# ProPrj.net
KiCad netlist of a schematic drawn in EasyEDA Pro
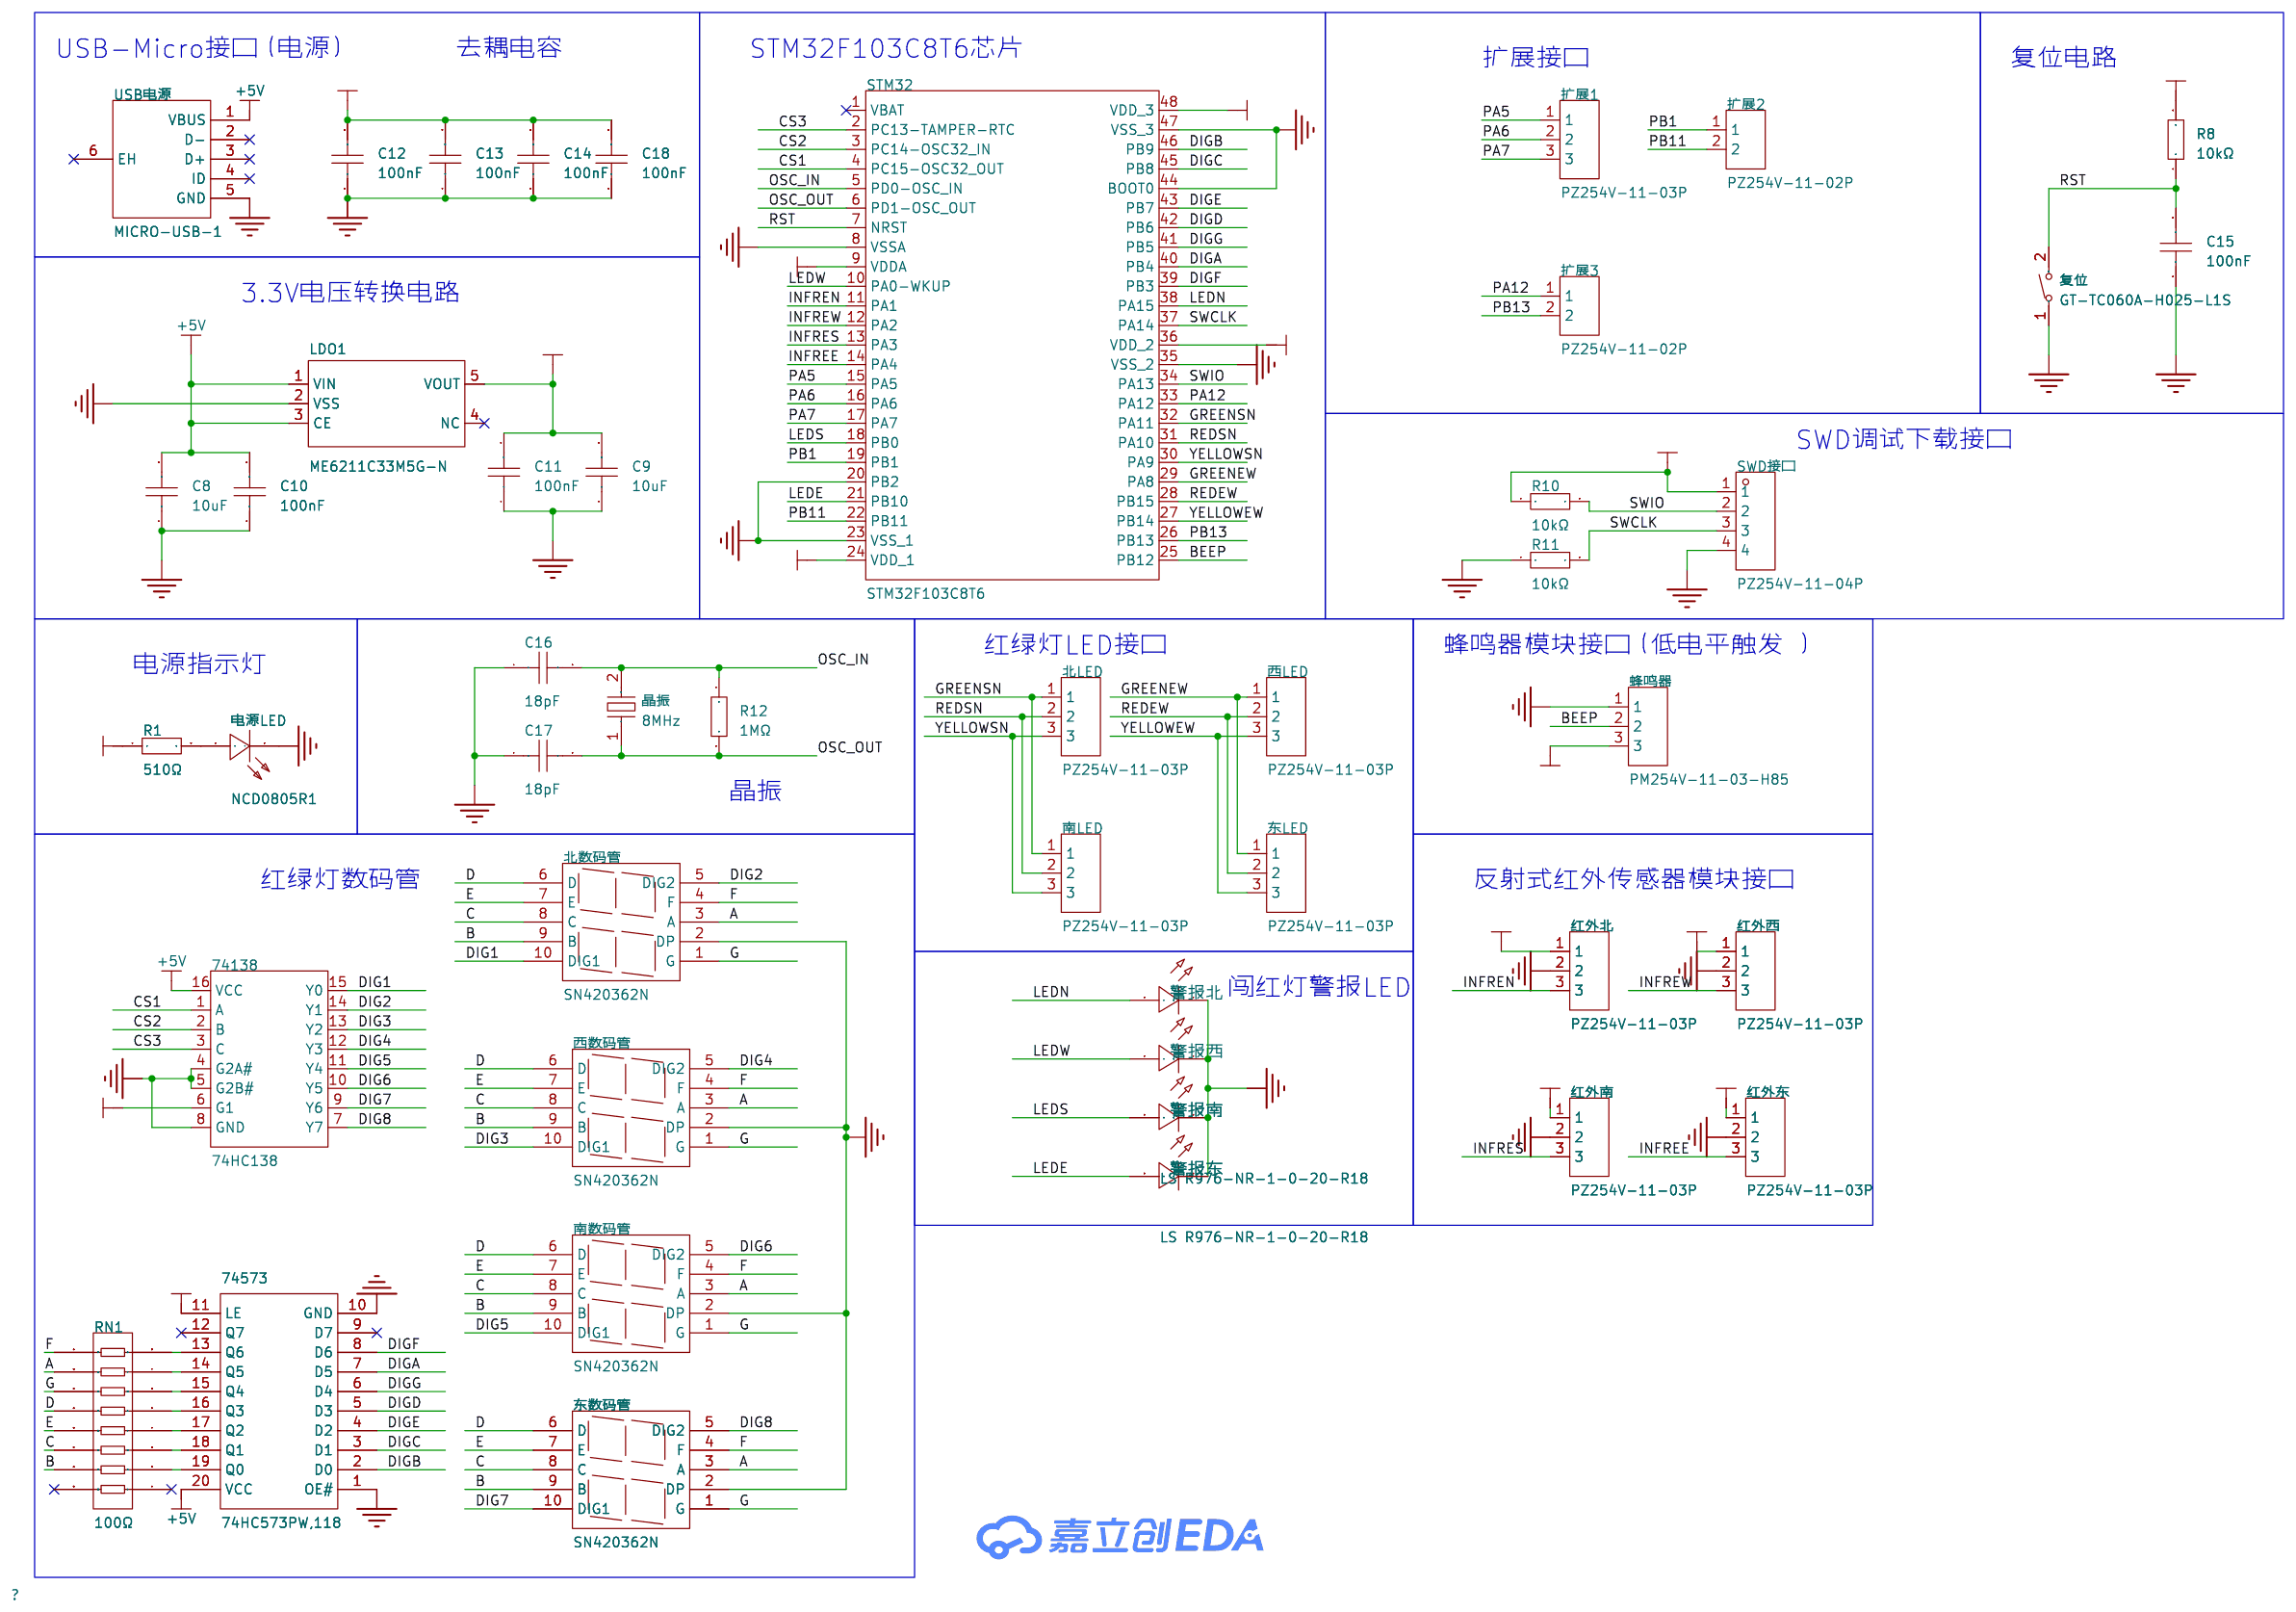
[diagram p0: schematic sheet]

(export (version "E")
  (design (tool "Eeschema 10.0.6"))
  (components
    (comp (ref "74138")
      (value "74HC138")
      (footprint "easyedapro:SOP-16_L10.0-W3.9-P1.27-LS6.0-BL")
      (description "供电电压:2V~6V;线路数:3~8;灌电流(IOL):5.2mA;拉电流(IOH):5.2mA;")
      (fields (field (name "Manufacturer") "GR(国睿)"))
      (libsource (lib "easyedapro") (part "74HC138_C18164491"))
    )
    (comp (ref "74573")
      (value "74HC573PW,118")
      (footprint "easyedapro:TSSOP-20_L6.5-W4.4-P0.65-LS6.4-BL")
      (description "逻辑类型:D型锁存器;电源电压:2V~6V;通道数:8;传播延迟:14ns;")
      (fields (field (name "Manufacturer") "Nexperia(安世)"))
      (libsource (lib "easyedapro") (part "74HC573PW,118"))
    )
    (comp (ref "C8")
      (value "10uF")
      (footprint "easyedapro:C0805")
      (description "容值:10uF;精度:±10%;额定电压:25V;温度系数:X5R;")
      (fields
        (field (name "Manufacturer Part") "CGA0805X5R106K250MT")
        (field (name "Manufacturer") "HRE(芯声)")
      )
      (libsource (lib "easyedapro") (part "CGA0805X5R106K250MT"))
    )
    (comp (ref "C9")
      (value "10uF")
      (footprint "easyedapro:C0805")
      (description "容值:10uF;精度:±10%;额定电压:25V;温度系数:X5R;")
      (fields
        (field (name "Manufacturer Part") "CGA0805X5R106K250MT")
        (field (name "Manufacturer") "HRE(芯声)")
      )
      (libsource (lib "easyedapro") (part "CGA0805X5R106K250MT"))
    )
    (comp (ref "C10")
      (value "100nF")
      (footprint "easyedapro:C0805")
      (description "容值:100nF;精度:±10%;额定电压:50V;材质(温度系数):X7R;")
      (fields
        (field (name "Manufacturer Part") "CC0805KRX7R9BB104")
        (field (name "Manufacturer") "YAGEO(国巨)")
      )
      (libsource (lib "easyedapro") (part "CC0805KRX7R9BB104"))
    )
    (comp (ref "C11")
      (value "100nF")
      (footprint "easyedapro:C0805")
      (description "容值:100nF;精度:±10%;额定电压:50V;材质(温度系数):X7R;")
      (fields
        (field (name "Manufacturer Part") "CC0805KRX7R9BB104")
        (field (name "Manufacturer") "YAGEO(国巨)")
      )
      (libsource (lib "easyedapro") (part "CC0805KRX7R9BB104"))
    )
    (comp (ref "C12")
      (value "100nF")
      (footprint "easyedapro:C0805")
      (description "容值:100nF;精度:±10%;额定电压:50V;材质(温度系数):X7R;")
      (fields
        (field (name "Manufacturer Part") "CC0805KRX7R9BB104")
        (field (name "Manufacturer") "YAGEO(国巨)")
      )
      (libsource (lib "easyedapro") (part "CC0805KRX7R9BB104"))
    )
    (comp (ref "C13")
      (value "100nF")
      (footprint "easyedapro:C0805")
      (description "容值:100nF;精度:±10%;额定电压:50V;材质(温度系数):X7R;")
      (fields
        (field (name "Manufacturer Part") "CC0805KRX7R9BB104")
        (field (name "Manufacturer") "YAGEO(国巨)")
      )
      (libsource (lib "easyedapro") (part "CC0805KRX7R9BB104"))
    )
    (comp (ref "C14")
      (value "100nF")
      (footprint "easyedapro:C0805")
      (description "容值:100nF;精度:±10%;额定电压:50V;材质(温度系数):X7R;")
      (fields
        (field (name "Manufacturer Part") "CC0805KRX7R9BB104")
        (field (name "Manufacturer") "YAGEO(国巨)")
      )
      (libsource (lib "easyedapro") (part "CC0805KRX7R9BB104"))
    )
    (comp (ref "C15")
      (value "100nF")
      (footprint "easyedapro:C0805")
      (description "容值:100nF;精度:±10%;额定电压:50V;材质(温度系数):X7R;")
      (fields
        (field (name "Manufacturer Part") "CC0805KRX7R9BB104")
        (field (name "Manufacturer") "YAGEO(国巨)")
      )
      (libsource (lib "easyedapro") (part "CC0805KRX7R9BB104"))
    )
    (comp (ref "C16")
      (value "18pF")
      (footprint "easyedapro:C0805")
      (description "容值:18pF;精度:±5%;额定电压:50V;温度系数:C0G;")
      (fields
        (field (name "Manufacturer Part") "CGA0805C0G180J500HT")
        (field (name "Manufacturer") "HRE(芯声)")
      )
      (libsource (lib "easyedapro") (part "CGA0805C0G180J500HT"))
    )
    (comp (ref "C17")
      (value "18pF")
      (footprint "easyedapro:C0805")
      (description "容值:18pF;精度:±5%;额定电压:50V;温度系数:C0G;")
      (fields
        (field (name "Manufacturer Part") "CGA0805C0G180J500HT")
        (field (name "Manufacturer") "HRE(芯声)")
      )
      (libsource (lib "easyedapro") (part "CGA0805C0G180J500HT"))
    )
    (comp (ref "C18")
      (value "100nF")
      (footprint "easyedapro:C0805")
      (description "容值:100nF;精度:±10%;额定电压:50V;材质(温度系数):X7R;")
      (fields
        (field (name "Manufacturer Part") "CC0805KRX7R9BB104")
        (field (name "Manufacturer") "YAGEO(国巨)")
      )
      (libsource (lib "easyedapro") (part "CC0805KRX7R9BB104"))
    )
    (comp (ref "LDO1")
      (value "ME6211C33M5G-N")
      (footprint "easyedapro:SOT-23-5_L3.0-W1.7-P0.95-LS2.8-BL")
      (description "输出类型:固定;工作电压:6V;输出电压:3.3V;输出电流:500mA;电源纹波抑制比(PSRR):70dB@(1kHz)；62dB@(10kHz);输出极性:正极;")
      (fields (field (name "Manufacturer") "MICRONE(南京微盟)"))
      (libsource (lib "easyedapro") (part "ME6211C33M5G-N"))
    )
    (comp (ref "R1")
      (value "510Ω")
      (footprint "easyedapro:R0805")
      (description "电阻类型:厚膜电阻;阻值:510Ω;精度:±1%;功率:125mW;最大工作电压:150V;温度系数:±100ppm/°C;")
      (fields
        (field (name "Manufacturer Part") "0805W8F5100T5E")
        (field (name "Manufacturer") "UNI-ROYAL(厚声)")
      )
      (libsource (lib "easyedapro") (part "0805W8F5100T5E"))
    )
    (comp (ref "R8")
      (value "10kΩ")
      (footprint "easyedapro:R0805")
      (description "电阻类型:厚膜电阻;阻值:10kΩ;精度:±1%;功率:125mW;最大工作电压:150V;温度系数:±100ppm/°C;")
      (fields
        (field (name "Manufacturer Part") "0805W8F1002T5E")
        (field (name "Manufacturer") "UNI-ROYAL(厚声)")
      )
      (libsource (lib "easyedapro") (part "0805W8F1002T5E"))
    )
    (comp (ref "R10")
      (value "10kΩ")
      (footprint "easyedapro:R0805")
      (description "电阻类型:厚膜电阻;阻值:10kΩ;精度:±1%;功率:125mW;最大工作电压:150V;温度系数:±100ppm/°C;")
      (fields
        (field (name "Manufacturer Part") "0805W8F1002T5E")
        (field (name "Manufacturer") "UNI-ROYAL(厚声)")
      )
      (libsource (lib "easyedapro") (part "0805W8F1002T5E"))
    )
    (comp (ref "R11")
      (value "10kΩ")
      (footprint "easyedapro:R0805")
      (description "电阻类型:厚膜电阻;阻值:10kΩ;精度:±1%;功率:125mW;最大工作电压:150V;温度系数:±100ppm/°C;")
      (fields
        (field (name "Manufacturer Part") "0805W8F1002T5E")
        (field (name "Manufacturer") "UNI-ROYAL(厚声)")
      )
      (libsource (lib "easyedapro") (part "0805W8F1002T5E"))
    )
    (comp (ref "R12")
      (value "1MΩ")
      (footprint "easyedapro:R0805")
      (description "电阻类型:厚膜电阻;阻值:1MΩ;精度:±1%;功率:125mW;最大工作电压:150V;温度系数:±100ppm/°C;")
      (fields
        (field (name "Manufacturer Part") "0805W8F1004T5E")
        (field (name "Manufacturer") "UNI-ROYAL(厚声)")
      )
      (libsource (lib "easyedapro") (part "0805W8F1004T5E"))
    )
    (comp (ref "RN1")
      (value "100Ω")
      (footprint "easyedapro:RES-ARRAY-SMD_16P-L3.8-W1.6-P0.50-BL")
      (description "电阻器数:8;阻值:100Ω;精度:±5%;单个元件功率:63mW;温度系数:±100ppm/°C;")
      (fields (field (name "Manufacturer Part") "EXB2HV101JV") (field (name "Manufacturer") "PANASONIC(松下)"))
      (libsource (lib "easyedapro") (part "EXB2HV101JV"))
    )
    (comp (ref "STM32")
      (value "STM32F103C8T6")
      (footprint "easyedapro:LQFP-48_L7.0-W7.0-P0.50-LS9.0-BL")
      (description "CPU内核:ARM-M3;CPU最大主频:72MHz;应用领域:-;")
      (fields (field (name "Manufacturer") "ST(意法半导体)"))
      (libsource (lib "easyedapro") (part "STM32F103C8T6"))
    )
    (comp (ref "SWD接口")
      (value "PZ254V-11-04P")
      (footprint "easyedapro:HDR-TH_4P-P2.54-V-M")
      (fields (field (name "Manufacturer") "XFCN(兴飞)"))
      (libsource (lib "easyedapro") (part "PZ254V-11-04P_C2691448"))
    )
    (comp (ref "USB电源")
      (value "MICRO-USB-1")
      (footprint "easyedapro:MICRO-USB-SMD_C9900008946")
      (libsource (lib "easyedapro") (part "MICRO-USB-1"))
    )
    (comp (ref "东LED")
      (value "PZ254V-11-03P")
      (footprint "easyedapro:HDR-TH_3P-P2.54-V-M")
      (fields (field (name "Manufacturer") "XFCN(兴飞)"))
      (libsource (lib "easyedapro") (part "PZ254V-11-03P_C2937625"))
    )
    (comp (ref "东数码管")
      (value "SN420362N")
      (footprint "easyedapro:LED-SEG-TH_10P-L15.0-W14.0-P2.54-S10.16-BL")
      (description "数码管位数:2位;耗散功率(Pd):50mW;发光颜色:红色;LED极性:共阴极;数字/字母大小(英寸):0.36;")
      (fields (field (name "Manufacturer") "ARKLED(方舟)"))
      (libsource (lib "easyedapro") (part "SN420362N"))
    )
    (comp (ref "北LED")
      (value "PZ254V-11-03P")
      (footprint "easyedapro:HDR-TH_3P-P2.54-V-M")
      (fields (field (name "Manufacturer") "XFCN(兴飞)"))
      (libsource (lib "easyedapro") (part "PZ254V-11-03P_C2937625"))
    )
    (comp (ref "北数码管")
      (value "SN420362N")
      (footprint "easyedapro:LED-SEG-TH_10P-L15.0-W14.0-P2.54-S10.16-BL")
      (description "数码管位数:2位;耗散功率(Pd):50mW;发光颜色:红色;LED极性:共阴极;数字/字母大小(英寸):0.36;")
      (fields (field (name "Manufacturer") "ARKLED(方舟)"))
      (libsource (lib "easyedapro") (part "SN420362N"))
    )
    (comp (ref "南LED")
      (value "PZ254V-11-03P")
      (footprint "easyedapro:HDR-TH_3P-P2.54-V-M")
      (fields (field (name "Manufacturer") "XFCN(兴飞)"))
      (libsource (lib "easyedapro") (part "PZ254V-11-03P_C2937625"))
    )
    (comp (ref "南数码管")
      (value "SN420362N")
      (footprint "easyedapro:LED-SEG-TH_10P-L15.0-W14.0-P2.54-S10.16-BL")
      (description "数码管位数:2位;耗散功率(Pd):50mW;发光颜色:红色;LED极性:共阴极;数字/字母大小(英寸):0.36;")
      (fields (field (name "Manufacturer") "ARKLED(方舟)"))
      (libsource (lib "easyedapro") (part "SN420362N"))
    )
    (comp (ref "复位")
      (value "GT-TC060A-H025-L1S")
      (footprint "easyedapro:SW-SMD_L6.1-W3.5-LS8.0")
      (description "电路结构:单刀单掷;作用力:1.6N;安装方式:立贴;带支架:不带;触点电流:50mA;额定电压(AC):12V;额定电压(DC):12V;绝缘电阻:100MΩ;带灯:无;机械寿命:10万次;")
      (fields (field (name "Manufacturer") "G-Switch(品赞)"))
      (libsource (lib "easyedapro") (part "GT-TC060A-H025-L1S"))
    )
    (comp (ref "扩展1")
      (value "PZ254V-11-03P")
      (footprint "easyedapro:HDR-TH_3P-P2.54-V-M")
      (fields (field (name "Manufacturer") "XFCN(兴飞)"))
      (libsource (lib "easyedapro") (part "PZ254V-11-03P_C2937625"))
    )
    (comp (ref "扩展2")
      (value "PZ254V-11-02P")
      (footprint "easyedapro:HDR-TH_2P-P2.54-V-M")
      (fields (field (name "Manufacturer") "XFCN(兴飞)"))
      (libsource (lib "easyedapro") (part "PZ254V-11-02P"))
    )
    (comp (ref "扩展3")
      (value "PZ254V-11-02P")
      (footprint "easyedapro:HDR-TH_2P-P2.54-V-M")
      (fields (field (name "Manufacturer") "XFCN(兴飞)"))
      (libsource (lib "easyedapro") (part "PZ254V-11-02P"))
    )
    (comp (ref "晶振")
      (value "8MHz")
      (footprint "easyedapro:HC-49US_L11.5-W4.5-P4.88")
      (description "频率:8MHz;常温频差:±20ppm;负载电容:18pF;频率稳定度(全温):±50ppm;")
      (fields (field (name "Manufacturer Part") "ABL-8.000MHZ-B2-T") (field (name "Manufacturer") "ABRACON"))
      (libsource (lib "easyedapro") (part "ABL-8.000MHZ-B2-T"))
    )
    (comp (ref "电源LED")
      (value "NCD0805R1")
      (footprint "easyedapro:LED0805-R-RD")
      (fields (field (name "Manufacturer") "国星光电"))
      (libsource (lib "easyedapro") (part "FC-2012HRK-620D"))
    )
    (comp (ref "红外东")
      (value "PZ254V-11-03P")
      (footprint "easyedapro:HDR-TH_3P-P2.54-V-M")
      (fields (field (name "Manufacturer") "XFCN(兴飞)"))
      (libsource (lib "easyedapro") (part "PZ254V-11-03P_C2937625"))
    )
    (comp (ref "红外北")
      (value "PZ254V-11-03P")
      (footprint "easyedapro:HDR-TH_3P-P2.54-V-M")
      (fields (field (name "Manufacturer") "XFCN(兴飞)"))
      (libsource (lib "easyedapro") (part "PZ254V-11-03P_C2937625"))
    )
    (comp (ref "红外南")
      (value "PZ254V-11-03P")
      (footprint "easyedapro:HDR-TH_3P-P2.54-V-M")
      (fields (field (name "Manufacturer") "XFCN(兴飞)"))
      (libsource (lib "easyedapro") (part "PZ254V-11-03P_C2937625"))
    )
    (comp (ref "红外西")
      (value "PZ254V-11-03P")
      (footprint "easyedapro:HDR-TH_3P-P2.54-V-M")
      (fields (field (name "Manufacturer") "XFCN(兴飞)"))
      (libsource (lib "easyedapro") (part "PZ254V-11-03P_C2937625"))
    )
    (comp (ref "蜂鸣器")
      (value "PM254V-11-03-H85")
      (footprint "easyedapro:HDR-TH_3P-P2.54-V-F")
      (description "插孔结构:1x3P;间距:2.54mm;行距:-;安装类型:直插;排数:单排;总孔位数:3P;塑高:-;触头材质:黄铜;触头镀层:-;")
      (fields (field (name "Manufacturer") "XFCN(兴飞)"))
      (libsource (lib "easyedapro") (part "PM254V-11-03-H85"))
    )
    (comp (ref "西LED")
      (value "PZ254V-11-03P")
      (footprint "easyedapro:HDR-TH_3P-P2.54-V-M")
      (fields (field (name "Manufacturer") "XFCN(兴飞)"))
      (libsource (lib "easyedapro") (part "PZ254V-11-03P_C2937625"))
    )
    (comp (ref "西数码管")
      (value "SN420362N")
      (footprint "easyedapro:LED-SEG-TH_10P-L15.0-W14.0-P2.54-S10.16-BL")
      (description "数码管位数:2位;耗散功率(Pd):50mW;发光颜色:红色;LED极性:共阴极;数字/字母大小(英寸):0.36;")
      (fields (field (name "Manufacturer") "ARKLED(方舟)"))
      (libsource (lib "easyedapro") (part "SN420362N"))
    )
    (comp (ref "警报东")
      (value "LS R976-NR-1-0-20-R18")
      (footprint "easyedapro:LED_0805")
      (fields (field (name "Manufacturer") "OSRAM(欧司朗)"))
      (libsource (lib "easyedapro") (part "LED_R"))
    )
    (comp (ref "警报北")
      (value "北")
      (footprint "easyedapro:LED_0805")
      (libsource (lib "easyedapro") (part "LED_R"))
    )
    (comp (ref "警报南")
      (value "LS R976-NR-1-0-20-R18")
      (footprint "easyedapro:LED_0805")
      (fields (field (name "Manufacturer") "OSRAM(欧司朗)"))
      (libsource (lib "easyedapro") (part "LED_R"))
    )
    (comp (ref "警报西")
      (value "西")
      (footprint "easyedapro:LED_0805")
      (libsource (lib "easyedapro") (part "LED_R"))
    )
  )
  (nets
    (net (code "1") (name "+5V") (class "Default")
      (node (ref "74138") (pin "16") (pinfunction "VCC_16") (pintype "unspecified"))
      (node (ref "74573") (pin "20") (pinfunction "VCC_20") (pintype "unspecified"))
      (node (ref "C10") (pin "2") (pinfunction "2_2") (pintype "unspecified"))
      (node (ref "C8") (pin "2") (pinfunction "2_2") (pintype "unspecified"))
      (node (ref "LDO1") (pin "1") (pinfunction "VIN_1") (pintype "unspecified"))
      (node (ref "LDO1") (pin "3") (pinfunction "CE_3") (pintype "unspecified"))
      (node (ref "USB电源") (pin "1") (pinfunction "VBUS_1") (pintype "input"))
    )
    (net (code "2") (name "/A") (class "Default")
      (node (ref "RN1") (pin "10") (pinfunction "10_10") (pintype "unspecified"))
      (node (ref "东数码管") (pin "3") (pinfunction "A_3") (pintype "unspecified"))
      (node (ref "北数码管") (pin "3") (pinfunction "A_3") (pintype "unspecified"))
      (node (ref "南数码管") (pin "3") (pinfunction "A_3") (pintype "unspecified"))
      (node (ref "西数码管") (pin "3") (pinfunction "A_3") (pintype "unspecified"))
    )
    (net (code "3") (name "/B") (class "Default")
      (node (ref "RN1") (pin "15") (pinfunction "15_15") (pintype "unspecified"))
      (node (ref "东数码管") (pin "9") (pinfunction "B_9") (pintype "unspecified"))
      (node (ref "北数码管") (pin "9") (pinfunction "B_9") (pintype "unspecified"))
      (node (ref "南数码管") (pin "9") (pinfunction "B_9") (pintype "unspecified"))
      (node (ref "西数码管") (pin "9") (pinfunction "B_9") (pintype "unspecified"))
    )
    (net (code "4") (name "/BEEP") (class "Default")
      (node (ref "STM32") (pin "25") (pinfunction "PB12_25") (pintype "unspecified"))
      (node (ref "蜂鸣器") (pin "2") (pinfunction "2_2") (pintype "unspecified"))
    )
    (net (code "5") (name "/C") (class "Default")
      (node (ref "RN1") (pin "14") (pinfunction "14_14") (pintype "unspecified"))
      (node (ref "东数码管") (pin "8") (pinfunction "C_8") (pintype "unspecified"))
      (node (ref "北数码管") (pin "8") (pinfunction "C_8") (pintype "unspecified"))
      (node (ref "南数码管") (pin "8") (pinfunction "C_8") (pintype "unspecified"))
      (node (ref "西数码管") (pin "8") (pinfunction "C_8") (pintype "unspecified"))
    )
    (net (code "6") (name "/CS1") (class "Default")
      (node (ref "74138") (pin "1") (pinfunction "A_1") (pintype "unspecified"))
      (node (ref "STM32") (pin "4") (pinfunction "PC15-OSC32_OUT_4") (pintype "unspecified"))
    )
    (net (code "7") (name "/CS2") (class "Default")
      (node (ref "74138") (pin "2") (pinfunction "B_2") (pintype "unspecified"))
      (node (ref "STM32") (pin "3") (pinfunction "PC14-OSC32_IN_3") (pintype "unspecified"))
    )
    (net (code "8") (name "/CS3") (class "Default")
      (node (ref "74138") (pin "3") (pinfunction "C_3") (pintype "unspecified"))
      (node (ref "STM32") (pin "2") (pinfunction "PC13-TAMPER-RTC_2") (pintype "unspecified"))
    )
    (net (code "9") (name "/D") (class "Default")
      (node (ref "RN1") (pin "12") (pinfunction "12_12") (pintype "unspecified"))
      (node (ref "东数码管") (pin "6") (pinfunction "D_6") (pintype "unspecified"))
      (node (ref "北数码管") (pin "6") (pinfunction "D_6") (pintype "unspecified"))
      (node (ref "南数码管") (pin "6") (pinfunction "D_6") (pintype "unspecified"))
      (node (ref "西数码管") (pin "6") (pinfunction "D_6") (pintype "unspecified"))
    )
    (net (code "10") (name "/DIG1") (class "Default")
      (node (ref "74138") (pin "15") (pinfunction "Y0_15") (pintype "unspecified"))
      (node (ref "北数码管") (pin "10") (pinfunction "DIG1_10") (pintype "unspecified"))
    )
    (net (code "11") (name "/DIG2") (class "Default")
      (node (ref "74138") (pin "14") (pinfunction "Y1_14") (pintype "unspecified"))
      (node (ref "北数码管") (pin "5") (pinfunction "DIG2_5") (pintype "unspecified"))
    )
    (net (code "12") (name "/DIG3") (class "Default")
      (node (ref "74138") (pin "13") (pinfunction "Y2_13") (pintype "unspecified"))
      (node (ref "西数码管") (pin "10") (pinfunction "DIG1_10") (pintype "unspecified"))
    )
    (net (code "13") (name "/DIG4") (class "Default")
      (node (ref "74138") (pin "12") (pinfunction "Y3_12") (pintype "unspecified"))
      (node (ref "西数码管") (pin "5") (pinfunction "DIG2_5") (pintype "unspecified"))
    )
    (net (code "14") (name "/DIG5") (class "Default")
      (node (ref "74138") (pin "11") (pinfunction "Y4_11") (pintype "unspecified"))
      (node (ref "南数码管") (pin "10") (pinfunction "DIG1_10") (pintype "unspecified"))
    )
    (net (code "15") (name "/DIG6") (class "Default")
      (node (ref "74138") (pin "10") (pinfunction "Y5_10") (pintype "unspecified"))
      (node (ref "南数码管") (pin "5") (pinfunction "DIG2_5") (pintype "unspecified"))
    )
    (net (code "16") (name "/DIG7") (class "Default")
      (node (ref "74138") (pin "9") (pinfunction "Y6_9") (pintype "unspecified"))
      (node (ref "东数码管") (pin "10") (pinfunction "DIG1_10") (pintype "unspecified"))
    )
    (net (code "17") (name "/DIG8") (class "Default")
      (node (ref "74138") (pin "7") (pinfunction "Y7_7") (pintype "unspecified"))
      (node (ref "东数码管") (pin "5") (pinfunction "DIG2_5") (pintype "unspecified"))
    )
    (net (code "18") (name "/DIGA") (class "Default")
      (node (ref "74573") (pin "7") (pinfunction "D5_7") (pintype "unspecified"))
      (node (ref "STM32") (pin "40") (pinfunction "PB4_40") (pintype "unspecified"))
    )
    (net (code "19") (name "/DIGB") (class "Default")
      (node (ref "74573") (pin "2") (pinfunction "D0_2") (pintype "unspecified"))
      (node (ref "STM32") (pin "46") (pinfunction "PB9_46") (pintype "unspecified"))
    )
    (net (code "20") (name "/DIGC") (class "Default")
      (node (ref "74573") (pin "3") (pinfunction "D1_3") (pintype "unspecified"))
      (node (ref "STM32") (pin "45") (pinfunction "PB8_45") (pintype "unspecified"))
    )
    (net (code "21") (name "/DIGD") (class "Default")
      (node (ref "74573") (pin "5") (pinfunction "D3_5") (pintype "unspecified"))
      (node (ref "STM32") (pin "42") (pinfunction "PB6_42") (pintype "unspecified"))
    )
    (net (code "22") (name "/DIGE") (class "Default")
      (node (ref "74573") (pin "4") (pinfunction "D2_4") (pintype "unspecified"))
      (node (ref "STM32") (pin "43") (pinfunction "PB7_43") (pintype "unspecified"))
    )
    (net (code "23") (name "/DIGF") (class "Default")
      (node (ref "74573") (pin "8") (pinfunction "D6_8") (pintype "unspecified"))
      (node (ref "STM32") (pin "39") (pinfunction "PB3_39") (pintype "unspecified"))
    )
    (net (code "24") (name "/DIGG") (class "Default")
      (node (ref "74573") (pin "6") (pinfunction "D4_6") (pintype "unspecified"))
      (node (ref "STM32") (pin "41") (pinfunction "PB5_41") (pintype "unspecified"))
    )
    (net (code "25") (name "/E") (class "Default")
      (node (ref "RN1") (pin "13") (pinfunction "13_13") (pintype "unspecified"))
      (node (ref "东数码管") (pin "7") (pinfunction "E_7") (pintype "unspecified"))
      (node (ref "北数码管") (pin "7") (pinfunction "E_7") (pintype "unspecified"))
      (node (ref "南数码管") (pin "7") (pinfunction "E_7") (pintype "unspecified"))
      (node (ref "西数码管") (pin "7") (pinfunction "E_7") (pintype "unspecified"))
    )
    (net (code "26") (name "/F") (class "Default")
      (node (ref "RN1") (pin "9") (pinfunction "9_9") (pintype "unspecified"))
      (node (ref "东数码管") (pin "4") (pinfunction "F_4") (pintype "unspecified"))
      (node (ref "北数码管") (pin "4") (pinfunction "F_4") (pintype "unspecified"))
      (node (ref "南数码管") (pin "4") (pinfunction "F_4") (pintype "unspecified"))
      (node (ref "西数码管") (pin "4") (pinfunction "F_4") (pintype "unspecified"))
    )
    (net (code "27") (name "/G") (class "Default")
      (node (ref "RN1") (pin "11") (pinfunction "11_11") (pintype "unspecified"))
      (node (ref "东数码管") (pin "1") (pinfunction "G_1") (pintype "unspecified"))
      (node (ref "北数码管") (pin "1") (pinfunction "G_1") (pintype "unspecified"))
      (node (ref "南数码管") (pin "1") (pinfunction "G_1") (pintype "unspecified"))
      (node (ref "西数码管") (pin "1") (pinfunction "G_1") (pintype "unspecified"))
    )
    (net (code "28") (name "/GREENEW") (class "Default")
      (node (ref "STM32") (pin "29") (pinfunction "PA8_29") (pintype "unspecified"))
      (node (ref "东LED") (pin "1") (pinfunction "1_1") (pintype "unspecified"))
      (node (ref "西LED") (pin "1") (pinfunction "1_1") (pintype "unspecified"))
    )
    (net (code "29") (name "/GREENSN") (class "Default")
      (node (ref "STM32") (pin "32") (pinfunction "PA11_32") (pintype "unspecified"))
      (node (ref "北LED") (pin "1") (pinfunction "1_1") (pintype "unspecified"))
      (node (ref "南LED") (pin "1") (pinfunction "1_1") (pintype "unspecified"))
    )
    (net (code "30") (name "/INFREE") (class "Default")
      (node (ref "STM32") (pin "14") (pinfunction "PA4_14") (pintype "unspecified"))
      (node (ref "红外东") (pin "3") (pinfunction "3_3") (pintype "unspecified"))
    )
    (net (code "31") (name "/INFREN") (class "Default")
      (node (ref "STM32") (pin "11") (pinfunction "PA1_11") (pintype "unspecified"))
      (node (ref "红外北") (pin "3") (pinfunction "3_3") (pintype "unspecified"))
    )
    (net (code "32") (name "/INFRES") (class "Default")
      (node (ref "STM32") (pin "13") (pinfunction "PA3_13") (pintype "unspecified"))
      (node (ref "红外南") (pin "3") (pinfunction "3_3") (pintype "unspecified"))
    )
    (net (code "33") (name "/INFREW") (class "Default")
      (node (ref "STM32") (pin "12") (pinfunction "PA2_12") (pintype "unspecified"))
      (node (ref "红外西") (pin "3") (pinfunction "3_3") (pintype "unspecified"))
    )
    (net (code "34") (name "/LEDE") (class "Default")
      (node (ref "STM32") (pin "21") (pinfunction "PB10_21") (pintype "unspecified"))
      (node (ref "警报东") (pin "2") (pinfunction "A_2") (pintype "input"))
    )
    (net (code "35") (name "/LEDN") (class "Default")
      (node (ref "STM32") (pin "38") (pinfunction "PA15_38") (pintype "unspecified"))
      (node (ref "警报北") (pin "2") (pinfunction "A_2") (pintype "input"))
    )
    (net (code "36") (name "/LEDS") (class "Default")
      (node (ref "STM32") (pin "18") (pinfunction "PB0_18") (pintype "unspecified"))
      (node (ref "警报南") (pin "2") (pinfunction "A_2") (pintype "input"))
    )
    (net (code "37") (name "/LEDW") (class "Default")
      (node (ref "STM32") (pin "10") (pinfunction "PA0-WKUP_10") (pintype "unspecified"))
      (node (ref "警报西") (pin "2") (pinfunction "A_2") (pintype "input"))
    )
    (net (code "38") (name "/OSC_IN") (class "Default")
      (node (ref "C16") (pin "2") (pinfunction "2_2") (pintype "unspecified"))
      (node (ref "R12") (pin "1") (pinfunction "1_1") (pintype "input"))
      (node (ref "STM32") (pin "5") (pinfunction "PD0-OSC_IN_5") (pintype "unspecified"))
      (node (ref "晶振") (pin "2") (pinfunction "2_2") (pintype "input"))
    )
    (net (code "39") (name "/OSC_OUT") (class "Default")
      (node (ref "C17") (pin "2") (pinfunction "2_2") (pintype "unspecified"))
      (node (ref "R12") (pin "2") (pinfunction "2_2") (pintype "input"))
      (node (ref "STM32") (pin "6") (pinfunction "PD1-OSC_OUT_6") (pintype "unspecified"))
      (node (ref "晶振") (pin "1") (pinfunction "1_1") (pintype "input"))
    )
    (net (code "40") (name "/PA5") (class "Default")
      (node (ref "STM32") (pin "15") (pinfunction "PA5_15") (pintype "unspecified"))
      (node (ref "扩展1") (pin "1") (pinfunction "1_1") (pintype "unspecified"))
    )
    (net (code "41") (name "/PA6") (class "Default")
      (node (ref "STM32") (pin "16") (pinfunction "PA6_16") (pintype "unspecified"))
      (node (ref "扩展1") (pin "2") (pinfunction "2_2") (pintype "unspecified"))
    )
    (net (code "42") (name "/PA7") (class "Default")
      (node (ref "STM32") (pin "17") (pinfunction "PA7_17") (pintype "unspecified"))
      (node (ref "扩展1") (pin "3") (pinfunction "3_3") (pintype "unspecified"))
    )
    (net (code "43") (name "/PA12") (class "Default")
      (node (ref "STM32") (pin "33") (pinfunction "PA12_33") (pintype "unspecified"))
      (node (ref "扩展3") (pin "1") (pinfunction "1_1") (pintype "unspecified"))
    )
    (net (code "44") (name "/PB1") (class "Default")
      (node (ref "STM32") (pin "19") (pinfunction "PB1_19") (pintype "unspecified"))
      (node (ref "扩展2") (pin "1") (pinfunction "1_1") (pintype "unspecified"))
    )
    (net (code "45") (name "/PB11") (class "Default")
      (node (ref "STM32") (pin "22") (pinfunction "PB11_22") (pintype "unspecified"))
      (node (ref "扩展2") (pin "2") (pinfunction "2_2") (pintype "unspecified"))
    )
    (net (code "46") (name "/PB13") (class "Default")
      (node (ref "STM32") (pin "26") (pinfunction "PB13_26") (pintype "unspecified"))
      (node (ref "扩展3") (pin "2") (pinfunction "2_2") (pintype "unspecified"))
    )
    (net (code "47") (name "/REDEW") (class "Default")
      (node (ref "STM32") (pin "28") (pinfunction "PB15_28") (pintype "unspecified"))
      (node (ref "东LED") (pin "2") (pinfunction "2_2") (pintype "unspecified"))
      (node (ref "西LED") (pin "2") (pinfunction "2_2") (pintype "unspecified"))
    )
    (net (code "48") (name "/REDSN") (class "Default")
      (node (ref "STM32") (pin "31") (pinfunction "PA10_31") (pintype "unspecified"))
      (node (ref "北LED") (pin "2") (pinfunction "2_2") (pintype "unspecified"))
      (node (ref "南LED") (pin "2") (pinfunction "2_2") (pintype "unspecified"))
    )
    (net (code "49") (name "/RST") (class "Default")
      (node (ref "C15") (pin "2") (pinfunction "2_2") (pintype "unspecified"))
      (node (ref "R8") (pin "1") (pinfunction "1_1") (pintype "input"))
      (node (ref "STM32") (pin "7") (pinfunction "NRST_7") (pintype "unspecified"))
      (node (ref "复位") (pin "2") (pinfunction "2_2") (pintype "unspecified"))
    )
    (net (code "50") (name "/SWCLK") (class "Default")
      (node (ref "R11") (pin "2") (pinfunction "2_2") (pintype "input"))
      (node (ref "STM32") (pin "37") (pinfunction "PA14_37") (pintype "unspecified"))
      (node (ref "SWD接口") (pin "3") (pinfunction "3_3") (pintype "unspecified"))
    )
    (net (code "51") (name "/SWIO") (class "Default")
      (node (ref "R10") (pin "2") (pinfunction "2_2") (pintype "input"))
      (node (ref "STM32") (pin "34") (pinfunction "PA13_34") (pintype "unspecified"))
      (node (ref "SWD接口") (pin "2") (pinfunction "2_2") (pintype "unspecified"))
    )
    (net (code "52") (name "/YELLOWEW") (class "Default")
      (node (ref "STM32") (pin "27") (pinfunction "PB14_27") (pintype "unspecified"))
      (node (ref "东LED") (pin "3") (pinfunction "3_3") (pintype "unspecified"))
      (node (ref "西LED") (pin "3") (pinfunction "3_3") (pintype "unspecified"))
    )
    (net (code "53") (name "/YELLOWSN") (class "Default")
      (node (ref "STM32") (pin "30") (pinfunction "PA9_30") (pintype "unspecified"))
      (node (ref "北LED") (pin "3") (pinfunction "3_3") (pintype "unspecified"))
      (node (ref "南LED") (pin "3") (pinfunction "3_3") (pintype "unspecified"))
    )
    (net (code "54") (name "GND") (class "Default")
      (node (ref "74138") (pin "4") (pinfunction "G2A#_4") (pintype "unspecified"))
      (node (ref "74138") (pin "5") (pinfunction "G2B#_5") (pintype "unspecified"))
      (node (ref "74138") (pin "8") (pinfunction "GND_8") (pintype "unspecified"))
      (node (ref "74573") (pin "1") (pinfunction "OE#_1") (pintype "unspecified"))
      (node (ref "74573") (pin "10") (pinfunction "GND_10") (pintype "unspecified"))
      (node (ref "C10") (pin "1") (pinfunction "1_1") (pintype "unspecified"))
      (node (ref "C11") (pin "1") (pinfunction "1_1") (pintype "unspecified"))
      (node (ref "C12") (pin "1") (pinfunction "1_1") (pintype "unspecified"))
      (node (ref "C13") (pin "1") (pinfunction "1_1") (pintype "unspecified"))
      (node (ref "C14") (pin "1") (pinfunction "1_1") (pintype "unspecified"))
      (node (ref "C15") (pin "1") (pinfunction "1_1") (pintype "unspecified"))
      (node (ref "C16") (pin "1") (pinfunction "1_1") (pintype "unspecified"))
      (node (ref "C17") (pin "1") (pinfunction "1_1") (pintype "unspecified"))
      (node (ref "C18") (pin "1") (pinfunction "1_1") (pintype "unspecified"))
      (node (ref "C8") (pin "1") (pinfunction "1_1") (pintype "unspecified"))
      (node (ref "C9") (pin "1") (pinfunction "1_1") (pintype "unspecified"))
      (node (ref "LDO1") (pin "2") (pinfunction "VSS_2") (pintype "unspecified"))
      (node (ref "R11") (pin "1") (pinfunction "1_1") (pintype "input"))
      (node (ref "STM32") (pin "20") (pinfunction "PB2_20") (pintype "unspecified"))
      (node (ref "STM32") (pin "23") (pinfunction "VSS_1_23") (pintype "unspecified"))
      (node (ref "STM32") (pin "35") (pinfunction "VSS_2_35") (pintype "unspecified"))
      (node (ref "STM32") (pin "44") (pinfunction "BOOT0_44") (pintype "unspecified"))
      (node (ref "STM32") (pin "47") (pinfunction "VSS_3_47") (pintype "unspecified"))
      (node (ref "STM32") (pin "8") (pinfunction "VSSA_8") (pintype "unspecified"))
      (node (ref "SWD接口") (pin "4") (pinfunction "4_4") (pintype "unspecified"))
      (node (ref "USB电源") (pin "5") (pinfunction "GND_5") (pintype "input"))
      (node (ref "东数码管") (pin "2") (pinfunction "DP_2") (pintype "unspecified"))
      (node (ref "北数码管") (pin "2") (pinfunction "DP_2") (pintype "unspecified"))
      (node (ref "南数码管") (pin "2") (pinfunction "DP_2") (pintype "unspecified"))
      (node (ref "复位") (pin "1") (pinfunction "1_1") (pintype "unspecified"))
      (node (ref "电源LED") (pin "2") (pinfunction "-_2") (pintype "unspecified"))
      (node (ref "红外东") (pin "2") (pinfunction "2_2") (pintype "unspecified"))
      (node (ref "红外北") (pin "2") (pinfunction "2_2") (pintype "unspecified"))
      (node (ref "红外南") (pin "2") (pinfunction "2_2") (pintype "unspecified"))
      (node (ref "红外西") (pin "2") (pinfunction "2_2") (pintype "unspecified"))
      (node (ref "蜂鸣器") (pin "1") (pinfunction "1_1") (pintype "unspecified"))
      (node (ref "西数码管") (pin "2") (pinfunction "DP_2") (pintype "unspecified"))
      (node (ref "警报东") (pin "1") (pinfunction "C_1") (pintype "input"))
      (node (ref "警报北") (pin "1") (pinfunction "C_1") (pintype "input"))
      (node (ref "警报南") (pin "1") (pinfunction "C_1") (pintype "input"))
      (node (ref "警报西") (pin "1") (pinfunction "C_1") (pintype "input"))
    )
    (net (code "55") (name "Net-(74573-Q0)") (class "Default")
      (node (ref "74573") (pin "19") (pinfunction "Q0_19") (pintype "unspecified"))
      (node (ref "RN1") (pin "2") (pinfunction "2_2") (pintype "unspecified"))
    )
    (net (code "56") (name "Net-(74573-Q1)") (class "Default")
      (node (ref "74573") (pin "18") (pinfunction "Q1_18") (pintype "unspecified"))
      (node (ref "RN1") (pin "3") (pinfunction "3_3") (pintype "unspecified"))
    )
    (net (code "57") (name "Net-(74573-Q2)") (class "Default")
      (node (ref "74573") (pin "17") (pinfunction "Q2_17") (pintype "unspecified"))
      (node (ref "RN1") (pin "4") (pinfunction "4_4") (pintype "unspecified"))
    )
    (net (code "58") (name "Net-(74573-Q3)") (class "Default")
      (node (ref "74573") (pin "16") (pinfunction "Q3_16") (pintype "unspecified"))
      (node (ref "RN1") (pin "5") (pinfunction "5_5") (pintype "unspecified"))
    )
    (net (code "59") (name "Net-(74573-Q4)") (class "Default")
      (node (ref "74573") (pin "15") (pinfunction "Q4_15") (pintype "unspecified"))
      (node (ref "RN1") (pin "6") (pinfunction "6_6") (pintype "unspecified"))
    )
    (net (code "60") (name "Net-(74573-Q5)") (class "Default")
      (node (ref "74573") (pin "14") (pinfunction "Q5_14") (pintype "unspecified"))
      (node (ref "RN1") (pin "7") (pinfunction "7_7") (pintype "unspecified"))
    )
    (net (code "61") (name "Net-(74573-Q6)") (class "Default")
      (node (ref "74573") (pin "13") (pinfunction "Q6_13") (pintype "unspecified"))
      (node (ref "RN1") (pin "8") (pinfunction "8_8") (pintype "unspecified"))
    )
    (net (code "62") (name "Net-(电源LED-+)") (class "Default")
      (node (ref "R1") (pin "2") (pinfunction "2_2") (pintype "input"))
      (node (ref "电源LED") (pin "1") (pinfunction "+_1") (pintype "unspecified"))
    )
    (net (code "63") (name "VCC_3V3") (class "Default")
      (node (ref "74138") (pin "6") (pinfunction "G1_6") (pintype "unspecified"))
      (node (ref "74573") (pin "11") (pinfunction "LE_11") (pintype "unspecified"))
      (node (ref "C11") (pin "2") (pinfunction "2_2") (pintype "unspecified"))
      (node (ref "C12") (pin "2") (pinfunction "2_2") (pintype "unspecified"))
      (node (ref "C13") (pin "2") (pinfunction "2_2") (pintype "unspecified"))
      (node (ref "C14") (pin "2") (pinfunction "2_2") (pintype "unspecified"))
      (node (ref "C18") (pin "2") (pinfunction "2_2") (pintype "unspecified"))
      (node (ref "C9") (pin "2") (pinfunction "2_2") (pintype "unspecified"))
      (node (ref "LDO1") (pin "5") (pinfunction "VOUT_5") (pintype "unspecified"))
      (node (ref "R1") (pin "1") (pinfunction "1_1") (pintype "input"))
      (node (ref "R10") (pin "1") (pinfunction "1_1") (pintype "input"))
      (node (ref "R8") (pin "2") (pinfunction "2_2") (pintype "input"))
      (node (ref "STM32") (pin "24") (pinfunction "VDD_1_24") (pintype "unspecified"))
      (node (ref "STM32") (pin "36") (pinfunction "VDD_2_36") (pintype "unspecified"))
      (node (ref "STM32") (pin "48") (pinfunction "VDD_3_48") (pintype "unspecified"))
      (node (ref "STM32") (pin "9") (pinfunction "VDDA_9") (pintype "unspecified"))
      (node (ref "SWD接口") (pin "1") (pinfunction "1_1") (pintype "unspecified"))
      (node (ref "红外东") (pin "1") (pinfunction "1_1") (pintype "unspecified"))
      (node (ref "红外北") (pin "1") (pinfunction "1_1") (pintype "unspecified"))
      (node (ref "红外南") (pin "1") (pinfunction "1_1") (pintype "unspecified"))
      (node (ref "红外西") (pin "1") (pinfunction "1_1") (pintype "unspecified"))
      (node (ref "蜂鸣器") (pin "3") (pinfunction "3_3") (pintype "unspecified"))
    )
    (net (code "64") (name "unconnected-(74573-D7-Pad9)") (class "Default")
      (node (ref "74573") (pin "9") (pinfunction "D7_9") (pintype "unspecified+no_connect"))
    )
    (net (code "65") (name "unconnected-(74573-Q7-Pad12)") (class "Default")
      (node (ref "74573") (pin "12") (pinfunction "Q7_12") (pintype "unspecified+no_connect"))
    )
    (net (code "66") (name "unconnected-(LDO1-NC-Pad4)") (class "Default")
      (node (ref "LDO1") (pin "4") (pinfunction "NC_4") (pintype "unspecified+no_connect"))
    )
    (net (code "67") (name "unconnected-(RN1-Pad1)") (class "Default")
      (node (ref "RN1") (pin "1") (pinfunction "1_1") (pintype "unspecified+no_connect"))
    )
    (net (code "68") (name "unconnected-(RN1-Pad16)") (class "Default")
      (node (ref "RN1") (pin "16") (pinfunction "16_16") (pintype "unspecified+no_connect"))
    )
    (net (code "69") (name "unconnected-(STM32-VBAT-Pad1)") (class "Default")
      (node (ref "STM32") (pin "1") (pinfunction "VBAT_1") (pintype "unspecified+no_connect"))
    )
    (net (code "70") (name "unconnected-(USB电源-D+-Pad3)") (class "Default")
      (node (ref "USB电源") (pin "3") (pinfunction "D+_3") (pintype "input+no_connect"))
    )
    (net (code "71") (name "unconnected-(USB电源-D--Pad2)") (class "Default")
      (node (ref "USB电源") (pin "2") (pinfunction "D-_2") (pintype "input+no_connect"))
    )
    (net (code "72") (name "unconnected-(USB电源-EH-Pad6)") (class "Default")
      (node (ref "USB电源") (pin "6") (pinfunction "EH_6") (pintype "input+no_connect"))
    )
    (net (code "73") (name "unconnected-(USB电源-ID-Pad4)") (class "Default")
      (node (ref "USB电源") (pin "4") (pinfunction "ID_4") (pintype "input+no_connect"))
    )
  )
)
